# ProPrj_RC-Plate_2025-08-21.net
KiCad netlist of a schematic drawn in EasyEDA Pro
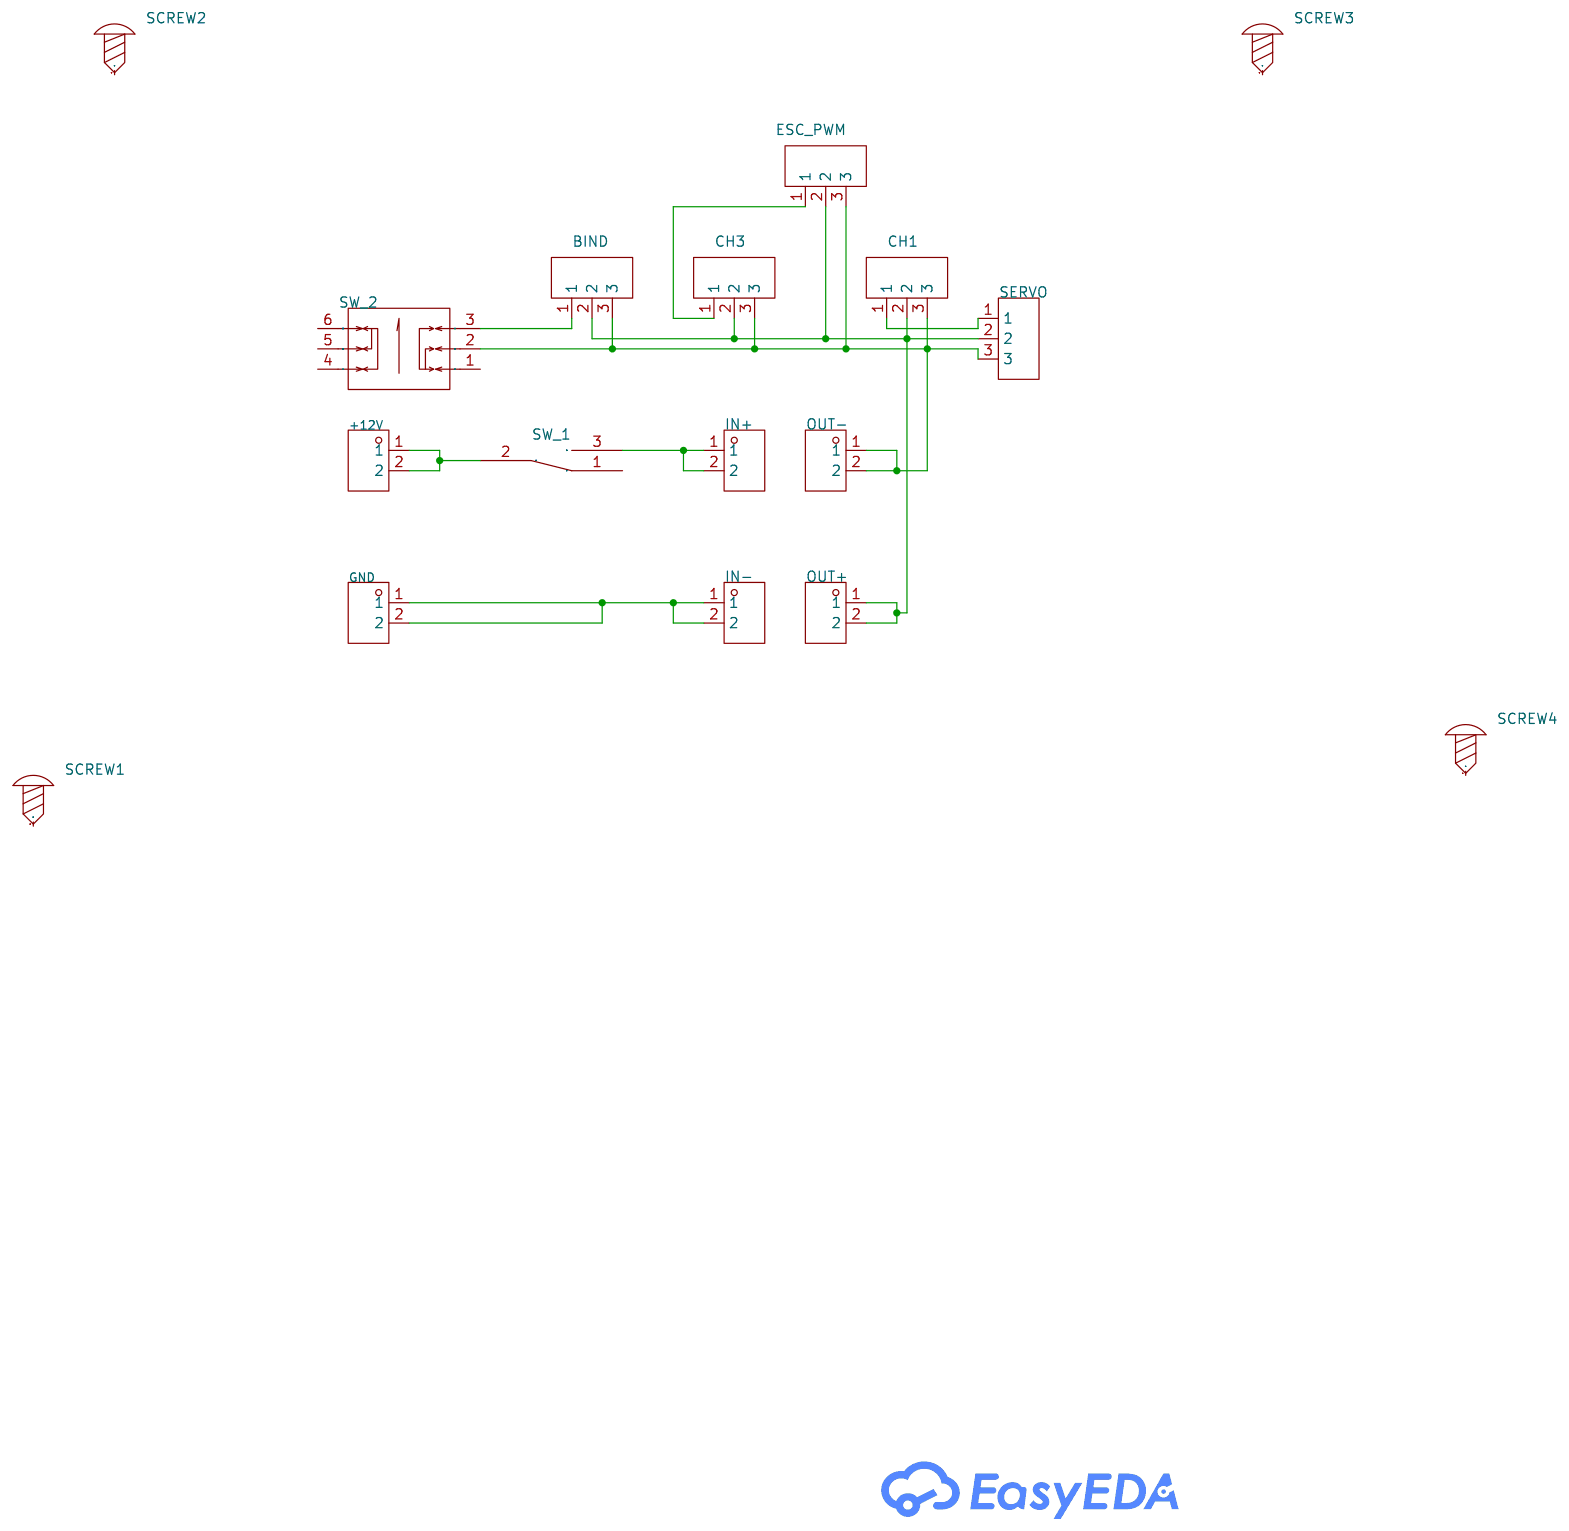
[diagram p0: schematic sheet]

(export (version "E")
  (design (tool "Eeschema 10.0.6"))
  (components
    (comp (ref "+12V")
      (value "KF301-5.0-2P")
      (footprint "easyedapro:CONN-TH_P5.00_KF301-5.0-2P")
      (fields (field (name "Manufacturer") "KEFA(科发)"))
      (libsource (lib "easyedapro") (part "KF301-5.0-2P"))
    )
    (comp (ref "BIND")
      (value "PM254V-11-03-H85")
      (footprint "easyedapro:HDR-TH_3P-P2.54-V-F")
      (fields (field (name "Manufacturer") "XFCN(兴飞)"))
      (libsource (lib "easyedapro") (part "PM254V-11-03-H85"))
    )
    (comp (ref "CH1")
      (value "PM254V-11-03-H85")
      (footprint "easyedapro:HDR-TH_3P-P2.54-V-F")
      (fields (field (name "Manufacturer") "XFCN(兴飞)"))
      (libsource (lib "easyedapro") (part "PM254V-11-03-H85"))
    )
    (comp (ref "CH3")
      (value "PM254V-11-03-H85")
      (footprint "easyedapro:HDR-TH_3P-P2.54-V-F")
      (fields (field (name "Manufacturer") "XFCN(兴飞)"))
      (libsource (lib "easyedapro") (part "PM254V-11-03-H85"))
    )
    (comp (ref "ESC_PWM")
      (value "PZ254V-11-03P")
      (footprint "easyedapro:HDR-TH_3P-P2.54-V-M")
      (fields (field (name "Manufacturer") "XFCN(兴飞)"))
      (libsource (lib "easyedapro") (part "PZ254V-11-03P_C2937625"))
    )
    (comp (ref "GND")
      (value "KF301-5.0-2P")
      (footprint "easyedapro:CONN-TH_P5.00_KF301-5.0-2P")
      (fields (field (name "Manufacturer") "KEFA(科发)"))
      (libsource (lib "easyedapro") (part "KF301-5.0-2P"))
    )
    (comp (ref "IN+")
      (value "ZX-PM2.54-1-2PY")
      (footprint "easyedapro:HDR-TH_2P-P2.54-V-F")
      (fields (field (name "Manufacturer") "Megastar(兆星)"))
      (libsource (lib "easyedapro") (part "ZX-PM2.54-1-2PY"))
    )
    (comp (ref "IN-")
      (value "ZX-PM2.54-1-2PY")
      (footprint "easyedapro:HDR-TH_2P-P2.54-V-F")
      (fields (field (name "Manufacturer") "Megastar(兆星)"))
      (libsource (lib "easyedapro") (part "ZX-PM2.54-1-2PY"))
    )
    (comp (ref "OUT+")
      (value "ZX-PM2.54-1-2PY")
      (footprint "easyedapro:HDR-TH_2P-P2.54-V-F")
      (fields (field (name "Manufacturer") "Megastar(兆星)"))
      (libsource (lib "easyedapro") (part "ZX-PM2.54-1-2PY"))
    )
    (comp (ref "OUT-")
      (value "ZX-PM2.54-1-2PY")
      (footprint "easyedapro:HDR-TH_2P-P2.54-V-F")
      (fields (field (name "Manufacturer") "Megastar(兆星)"))
      (libsource (lib "easyedapro") (part "ZX-PM2.54-1-2PY"))
    )
    (comp (ref "SCREW1")
      (value "~")
      (footprint "easyedapro:Screw-Hole-M2")
      (libsource (lib "easyedapro") (part "Screw-Hole"))
    )
    (comp (ref "SCREW2")
      (value "~")
      (footprint "easyedapro:Screw-Hole-M2")
      (libsource (lib "easyedapro") (part "Screw-Hole"))
    )
    (comp (ref "SCREW3")
      (value "~")
      (footprint "easyedapro:Screw-Hole-M2")
      (libsource (lib "easyedapro") (part "Screw-Hole"))
    )
    (comp (ref "SCREW4")
      (value "~")
      (footprint "easyedapro:Screw-Hole-M2")
      (libsource (lib "easyedapro") (part "Screw-Hole"))
    )
    (comp (ref "SERVO")
      (value "PZ254V-11-03P")
      (footprint "easyedapro:HDR-TH_3P-P2.54-V-M")
      (fields (field (name "Manufacturer") "XFCN(兴飞)"))
      (libsource (lib "easyedapro") (part "PZ254V-11-03P_C2937625"))
    )
    (comp (ref "SW_1")
      (value "ST-0-102-A01-T000-LF")
      (footprint "easyedapro:SW-TH_3P-L8.3-W5.2-P2.54_ST-0-102-A01-T000")
      (fields (field (name "Manufacturer") "YUEN FUNG(源丰)"))
      (libsource (lib "easyedapro") (part "ST-0-102-A01-T000-LF+PJ"))
    )
    (comp (ref "SW_2")
      (value "8-8 ZS")
      (footprint "easyedapro:SW-TH_6P-L8.0-W8.0-P2.50-TL")
      (fields (field (name "Manufacturer") "SHOU HAN(首韩)"))
      (libsource (lib "easyedapro") (part "8-8 ZS"))
    )
  )
  (nets
    (net (code "1") (name "Net-(+12V-Pad1)") (class "Default")
      (node (ref "+12V") (pin "1") (pinfunction "1_1") (pintype "input"))
      (node (ref "+12V") (pin "2") (pinfunction "2_2") (pintype "input"))
      (node (ref "SW_1") (pin "2") (pinfunction "2_2") (pintype "unspecified"))
    )
    (net (code "2") (name "Net-(BIND-Pad1)") (class "Default")
      (node (ref "BIND") (pin "1") (pinfunction "1_1") (pintype "unspecified"))
      (node (ref "SW_2") (pin "3") (pinfunction "3_3") (pintype "unspecified"))
    )
    (net (code "3") (name "Net-(BIND-Pad2)") (class "Default")
      (node (ref "BIND") (pin "2") (pinfunction "2_2") (pintype "unspecified"))
      (node (ref "CH1") (pin "2") (pinfunction "2_2") (pintype "unspecified"))
      (node (ref "CH3") (pin "2") (pinfunction "2_2") (pintype "unspecified"))
      (node (ref "ESC_PWM") (pin "2") (pinfunction "2_2") (pintype "unspecified"))
      (node (ref "OUT+") (pin "1") (pinfunction "1_1") (pintype "unspecified"))
      (node (ref "OUT+") (pin "2") (pinfunction "2_2") (pintype "unspecified"))
      (node (ref "SERVO") (pin "2") (pinfunction "2_2") (pintype "unspecified"))
    )
    (net (code "4") (name "Net-(BIND-Pad3)") (class "Default")
      (node (ref "BIND") (pin "3") (pinfunction "3_3") (pintype "unspecified"))
      (node (ref "CH1") (pin "3") (pinfunction "3_3") (pintype "unspecified"))
      (node (ref "CH3") (pin "3") (pinfunction "3_3") (pintype "unspecified"))
      (node (ref "ESC_PWM") (pin "3") (pinfunction "3_3") (pintype "unspecified"))
      (node (ref "OUT-") (pin "1") (pinfunction "1_1") (pintype "unspecified"))
      (node (ref "OUT-") (pin "2") (pinfunction "2_2") (pintype "unspecified"))
      (node (ref "SERVO") (pin "3") (pinfunction "3_3") (pintype "unspecified"))
      (node (ref "SW_2") (pin "2") (pinfunction "2_2") (pintype "unspecified"))
    )
    (net (code "5") (name "Net-(CH1-Pad1)") (class "Default")
      (node (ref "CH1") (pin "1") (pinfunction "1_1") (pintype "unspecified"))
      (node (ref "SERVO") (pin "1") (pinfunction "1_1") (pintype "unspecified"))
    )
    (net (code "6") (name "Net-(CH3-Pad1)") (class "Default")
      (node (ref "CH3") (pin "1") (pinfunction "1_1") (pintype "unspecified"))
      (node (ref "ESC_PWM") (pin "1") (pinfunction "1_1") (pintype "unspecified"))
    )
    (net (code "7") (name "Net-(GND-Pad1)") (class "Default")
      (node (ref "GND") (pin "1") (pinfunction "1_1") (pintype "input"))
      (node (ref "GND") (pin "2") (pinfunction "2_2") (pintype "input"))
      (node (ref "IN-") (pin "1") (pinfunction "1_1") (pintype "unspecified"))
      (node (ref "IN-") (pin "2") (pinfunction "2_2") (pintype "unspecified"))
    )
    (net (code "8") (name "Net-(IN+-Pad1)") (class "Default")
      (node (ref "IN+") (pin "1") (pinfunction "1_1") (pintype "unspecified"))
      (node (ref "IN+") (pin "2") (pinfunction "2_2") (pintype "unspecified"))
      (node (ref "SW_1") (pin "3") (pinfunction "3_3") (pintype "unspecified"))
    )
    (net (code "9") (name "unconnected-(SCREW1-Pad1)") (class "Default")
      (node (ref "SCREW1") (pin "1") (pinfunction "1_1") (pintype "input"))
    )
    (net (code "10") (name "unconnected-(SCREW2-Pad1)") (class "Default")
      (node (ref "SCREW2") (pin "1") (pinfunction "1_1") (pintype "input"))
    )
    (net (code "11") (name "unconnected-(SCREW3-Pad1)") (class "Default")
      (node (ref "SCREW3") (pin "1") (pinfunction "1_1") (pintype "input"))
    )
    (net (code "12") (name "unconnected-(SCREW4-Pad1)") (class "Default")
      (node (ref "SCREW4") (pin "1") (pinfunction "1_1") (pintype "input"))
    )
    (net (code "13") (name "unconnected-(SW_1-Pad1)") (class "Default")
      (node (ref "SW_1") (pin "1") (pinfunction "1_1") (pintype "unspecified"))
    )
    (net (code "14") (name "unconnected-(SW_2-Pad1)") (class "Default")
      (node (ref "SW_2") (pin "1") (pinfunction "1_1") (pintype "unspecified"))
    )
    (net (code "15") (name "unconnected-(SW_2-Pad4)") (class "Default")
      (node (ref "SW_2") (pin "4") (pinfunction "4_4") (pintype "unspecified"))
    )
    (net (code "16") (name "unconnected-(SW_2-Pad5)") (class "Default")
      (node (ref "SW_2") (pin "5") (pinfunction "5_5") (pintype "unspecified"))
    )
    (net (code "17") (name "unconnected-(SW_2-Pad6)") (class "Default")
      (node (ref "SW_2") (pin "6") (pinfunction "6_6") (pintype "unspecified"))
    )
  )
)
